# otto.net
KiCad netlist of a schematic drawn in EAGLE
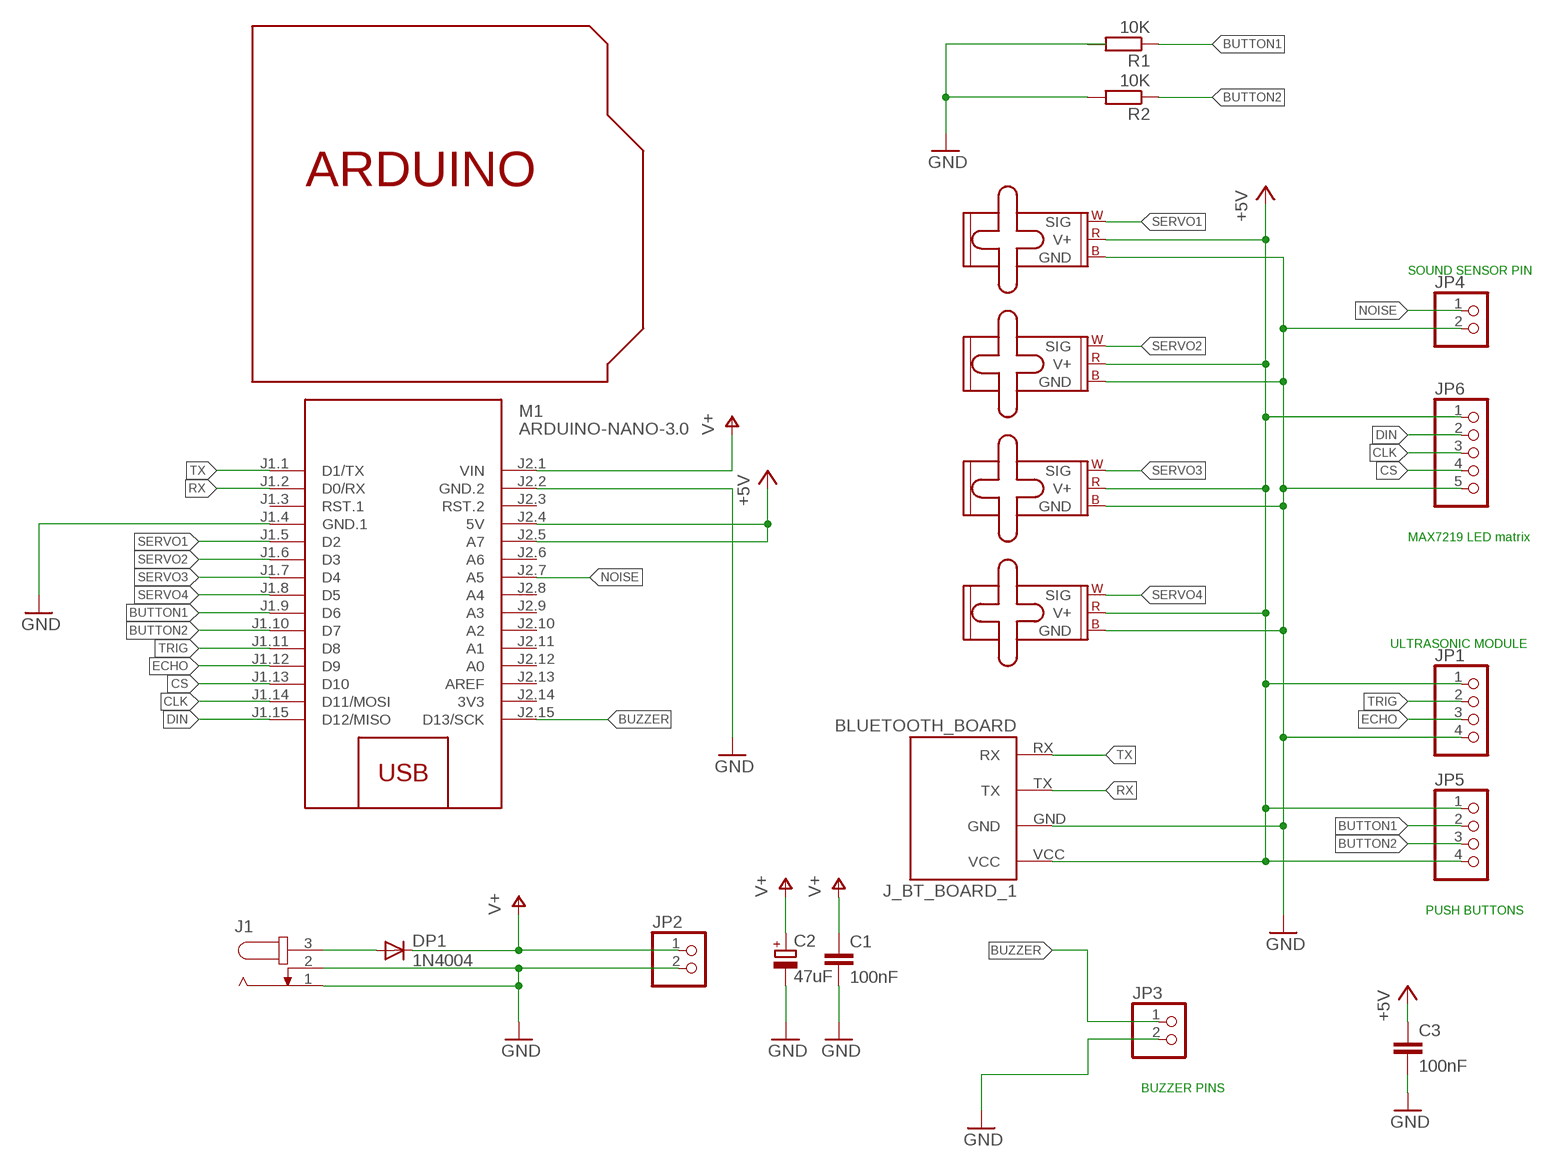
[diagram p0: schematic, sheet 1]

(export (version "E")
  (design (tool "Eeschema 10.0.6"))
  (components
    (comp (ref "C1")
      (value "100nF")
      (footprint "eagle-import:C025-025X050")
      (libsource (lib "eagle-import") (part "C-EU025-025X050"))
    )
    (comp (ref "C2")
      (value "47uF")
      (footprint "eagle-import:140CLH-0810")
      (libsource (lib "eagle-import") (part "CPOL-EU140CLH-0810"))
    )
    (comp (ref "C3")
      (value "100nF")
      (footprint "eagle-import:C025-025X050")
      (libsource (lib "eagle-import") (part "C-EU025-025X050"))
    )
    (comp (ref "DP1")
      (value "1N4004")
      (footprint "eagle-import:DO41-10")
      (libsource (lib "eagle-import") (part "1N4004"))
    )
    (comp (ref "J1")
      (value "JACK-PLUG0")
      (footprint "eagle-import:SPC4077")
      (libsource (lib "eagle-import") (part "JACK-PLUG0"))
    )
    (comp (ref "JP1")
      (value "PINHD-1X4")
      (footprint "eagle-import:1X04")
      (libsource (lib "eagle-import") (part "PINHD-1X4"))
    )
    (comp (ref "JP2")
      (value "PINHD-1X2")
      (footprint "eagle-import:1X02")
      (libsource (lib "eagle-import") (part "PINHD-1X2"))
    )
    (comp (ref "JP3")
      (value "PINHD-1X2")
      (footprint "eagle-import:1X02")
      (libsource (lib "eagle-import") (part "PINHD-1X2"))
    )
    (comp (ref "JP4")
      (value "PINHD-1X2")
      (footprint "eagle-import:1X02")
      (libsource (lib "eagle-import") (part "PINHD-1X2"))
    )
    (comp (ref "JP5")
      (value "PINHD-1X4")
      (footprint "eagle-import:1X04")
      (libsource (lib "eagle-import") (part "PINHD-1X4"))
    )
    (comp (ref "JP6")
      (value "PINHD-1X5")
      (footprint "eagle-import:1X05")
      (libsource (lib "eagle-import") (part "PINHD-1X5"))
    )
    (comp (ref "J_BT_BOARD_1")
      (value "BLUETOOTH_BOARD")
      (footprint "eagle-import:BT_BOARD_FOOTPRINT")
      (libsource (lib "eagle-import") (part "BLUETOOTH_BOARD"))
    )
    (comp (ref "M1")
      (value "ARDUINO-NANO-3.0")
      (footprint "eagle-import:ARDUINO-NANO-3.0")
      (libsource (lib "eagle-import") (part "ARDUINO-NANO-3.0"))
    )
    (comp (ref "M2")
      (value "SMALL_SERVO")
      (footprint "eagle-import:1X03")
      (libsource (lib "eagle-import") (part "SMALL_SERVO"))
    )
    (comp (ref "M3")
      (value "SMALL_SERVO")
      (footprint "eagle-import:1X03")
      (libsource (lib "eagle-import") (part "SMALL_SERVO"))
    )
    (comp (ref "M4")
      (value "SMALL_SERVO")
      (footprint "eagle-import:1X03")
      (libsource (lib "eagle-import") (part "SMALL_SERVO"))
    )
    (comp (ref "M5")
      (value "SMALL_SERVO")
      (footprint "eagle-import:1X03")
      (libsource (lib "eagle-import") (part "SMALL_SERVO"))
    )
    (comp (ref "R1")
      (value "10K")
      (footprint "eagle-import:0207_7")
      (libsource (lib "eagle-import") (part "R-EU_0207/7"))
    )
    (comp (ref "R2")
      (value "10K")
      (footprint "eagle-import:0207_7")
      (libsource (lib "eagle-import") (part "R-EU_0207/7"))
    )
    (comp (ref "U$1")
      (value "SHIELDSMALL")
      (footprint "eagle-import:ARDUINOSHIELDSMALL")
      (libsource (lib "eagle-import") (part "SHIELDSMALL"))
    )
  )
  (nets
    (net (code "1") (name "+5V") (class "Default")
      (node (ref "C3") (pin "1") (pinfunction "1_1") (pintype "passive"))
      (node (ref "JP1") (pin "1") (pinfunction "1_1") (pintype "passive"))
      (node (ref "JP5") (pin "1") (pinfunction "1_1") (pintype "passive"))
      (node (ref "JP5") (pin "4") (pinfunction "4_4") (pintype "passive"))
      (node (ref "JP6") (pin "1") (pinfunction "1_1") (pintype "passive"))
      (node (ref "J_BT_BOARD_1") (pin "VCC") (pinfunction "VCC_VCC") (pintype "bidirectional"))
      (node (ref "M1") (pin "J2.4") (pinfunction "5V_J2.4") (pintype "power_in"))
      (node (ref "M1") (pin "J2.5") (pinfunction "A7_J2.5") (pintype "bidirectional"))
      (node (ref "M2") (pin "2") (pinfunction "V+_2") (pintype "bidirectional"))
      (node (ref "M3") (pin "2") (pinfunction "V+_2") (pintype "bidirectional"))
      (node (ref "M4") (pin "2") (pinfunction "V+_2") (pintype "bidirectional"))
      (node (ref "M5") (pin "2") (pinfunction "V+_2") (pintype "bidirectional"))
    )
    (net (code "2") (name "/3V3") (class "Default")
      (node (ref "M1") (pin "J2.14") (pinfunction "3V3_J2.14") (pintype "power_in"))
    )
    (net (code "3") (name "BUTTON1") (class "Default")
      (node (ref "JP5") (pin "2") (pinfunction "2_2") (pintype "passive"))
      (node (ref "M1") (pin "J1.9") (pinfunction "D6_J1.9") (pintype "bidirectional"))
      (node (ref "R1") (pin "1") (pinfunction "1_1") (pintype "passive"))
    )
    (net (code "4") (name "BUTTON2") (class "Default")
      (node (ref "JP5") (pin "3") (pinfunction "3_3") (pintype "passive"))
      (node (ref "M1") (pin "J1.10") (pinfunction "D7_J1.10") (pintype "bidirectional"))
      (node (ref "R2") (pin "1") (pinfunction "1_1") (pintype "passive"))
    )
    (net (code "5") (name "BUZZER") (class "Default")
      (node (ref "JP3") (pin "1") (pinfunction "1_1") (pintype "passive"))
      (node (ref "M1") (pin "J2.15") (pinfunction "D13/SCK_J2.15") (pintype "bidirectional"))
    )
    (net (code "6") (name "CLK") (class "Default")
      (node (ref "JP6") (pin "3") (pinfunction "3_3") (pintype "passive"))
      (node (ref "M1") (pin "J1.14") (pinfunction "D11/MOSI_J1.14") (pintype "bidirectional"))
    )
    (net (code "7") (name "CS") (class "Default")
      (node (ref "JP6") (pin "4") (pinfunction "4_4") (pintype "passive"))
      (node (ref "M1") (pin "J1.13") (pinfunction "D10_J1.13") (pintype "bidirectional"))
    )
    (net (code "8") (name "DIN") (class "Default")
      (node (ref "JP6") (pin "2") (pinfunction "2_2") (pintype "passive"))
      (node (ref "M1") (pin "J1.15") (pinfunction "D12/MISO_J1.15") (pintype "bidirectional"))
    )
    (net (code "9") (name "ECHO") (class "Default")
      (node (ref "JP1") (pin "3") (pinfunction "3_3") (pintype "passive"))
      (node (ref "M1") (pin "J1.12") (pinfunction "D9_J1.12") (pintype "bidirectional"))
    )
    (net (code "10") (name "GND") (class "Default")
      (node (ref "C1") (pin "2") (pinfunction "2_2") (pintype "passive"))
      (node (ref "C2") (pin "-") (pinfunction "-_-") (pintype "passive"))
      (node (ref "C3") (pin "2") (pinfunction "2_2") (pintype "passive"))
      (node (ref "J1") (pin "1") (pinfunction "1_1") (pintype "passive"))
      (node (ref "J1") (pin "2") (pinfunction "2_2") (pintype "passive"))
      (node (ref "JP1") (pin "4") (pinfunction "4_4") (pintype "passive"))
      (node (ref "JP2") (pin "2") (pinfunction "2_2") (pintype "passive"))
      (node (ref "JP3") (pin "2") (pinfunction "2_2") (pintype "passive"))
      (node (ref "JP4") (pin "2") (pinfunction "2_2") (pintype "passive"))
      (node (ref "JP6") (pin "5") (pinfunction "5_5") (pintype "passive"))
      (node (ref "J_BT_BOARD_1") (pin "GND") (pinfunction "GND_GND") (pintype "bidirectional"))
      (node (ref "M1") (pin "J1.4") (pinfunction "GND.1_J1.4") (pintype "power_in"))
      (node (ref "M1") (pin "J2.2") (pinfunction "GND.2_J2.2") (pintype "power_in"))
      (node (ref "M2") (pin "3") (pinfunction "GND_3") (pintype "bidirectional"))
      (node (ref "M3") (pin "3") (pinfunction "GND_3") (pintype "bidirectional"))
      (node (ref "M4") (pin "3") (pinfunction "GND_3") (pintype "bidirectional"))
      (node (ref "M5") (pin "3") (pinfunction "GND_3") (pintype "bidirectional"))
      (node (ref "R2") (pin "2") (pinfunction "2_2") (pintype "passive"))
    )
    (net (code "11") (name "NOISE") (class "Default")
      (node (ref "JP4") (pin "1") (pinfunction "1_1") (pintype "passive"))
      (node (ref "M1") (pin "J2.7") (pinfunction "A5_J2.7") (pintype "bidirectional"))
    )
    (net (code "12") (name "Net-(DP1-PadA)") (class "Default")
      (node (ref "DP1") (pin "A") (pinfunction "A_A") (pintype "passive"))
      (node (ref "J1") (pin "3") (pinfunction "3_3") (pintype "passive"))
    )
    (net (code "13") (name "RX") (class "Default")
      (node (ref "J_BT_BOARD_1") (pin "TX") (pinfunction "TX_TX") (pintype "bidirectional"))
      (node (ref "M1") (pin "J1.2") (pinfunction "D0/RX_J1.2") (pintype "bidirectional"))
    )
    (net (code "14") (name "SERVO1") (class "Default")
      (node (ref "M1") (pin "J1.5") (pinfunction "D2_J1.5") (pintype "bidirectional"))
      (node (ref "M2") (pin "1") (pinfunction "SIG_1") (pintype "bidirectional"))
    )
    (net (code "15") (name "SERVO2") (class "Default")
      (node (ref "M1") (pin "J1.6") (pinfunction "D3_J1.6") (pintype "bidirectional"))
      (node (ref "M3") (pin "1") (pinfunction "SIG_1") (pintype "bidirectional"))
    )
    (net (code "16") (name "SERVO3") (class "Default")
      (node (ref "M1") (pin "J1.7") (pinfunction "D4_J1.7") (pintype "bidirectional"))
      (node (ref "M4") (pin "1") (pinfunction "SIG_1") (pintype "bidirectional"))
    )
    (net (code "17") (name "SERVO4") (class "Default")
      (node (ref "M1") (pin "J1.8") (pinfunction "D5_J1.8") (pintype "bidirectional"))
      (node (ref "M5") (pin "1") (pinfunction "SIG_1") (pintype "bidirectional"))
    )
    (net (code "18") (name "TRIG") (class "Default")
      (node (ref "JP1") (pin "2") (pinfunction "2_2") (pintype "passive"))
      (node (ref "M1") (pin "J1.11") (pinfunction "D8_J1.11") (pintype "bidirectional"))
    )
    (net (code "19") (name "TX") (class "Default")
      (node (ref "J_BT_BOARD_1") (pin "RX") (pinfunction "RX_RX") (pintype "bidirectional"))
      (node (ref "M1") (pin "J1.1") (pinfunction "D1/TX_J1.1") (pintype "bidirectional"))
    )
    (net (code "20") (name "V+") (class "Default")
      (node (ref "C1") (pin "1") (pinfunction "1_1") (pintype "passive"))
      (node (ref "C2") (pin "+") (pinfunction "+_+") (pintype "passive"))
      (node (ref "DP1") (pin "C") (pinfunction "C_C") (pintype "passive"))
      (node (ref "JP2") (pin "1") (pinfunction "1_1") (pintype "passive"))
      (node (ref "M1") (pin "J2.1") (pinfunction "VIN_J2.1") (pintype "power_in"))
    )
    (net (code "21") (name "unconnected-(M1-A0-PadJ2.12)") (class "Default")
      (node (ref "M1") (pin "J2.12") (pinfunction "A0_J2.12") (pintype "bidirectional"))
    )
    (net (code "22") (name "unconnected-(M1-A1-PadJ2.11)") (class "Default")
      (node (ref "M1") (pin "J2.11") (pinfunction "A1_J2.11") (pintype "bidirectional"))
    )
    (net (code "23") (name "unconnected-(M1-A2-PadJ2.10)") (class "Default")
      (node (ref "M1") (pin "J2.10") (pinfunction "A2_J2.10") (pintype "bidirectional"))
    )
    (net (code "24") (name "unconnected-(M1-A3-PadJ2.9)") (class "Default")
      (node (ref "M1") (pin "J2.9") (pinfunction "A3_J2.9") (pintype "bidirectional"))
    )
    (net (code "25") (name "unconnected-(M1-A4-PadJ2.8)") (class "Default")
      (node (ref "M1") (pin "J2.8") (pinfunction "A4_J2.8") (pintype "bidirectional"))
    )
    (net (code "26") (name "unconnected-(M1-A6-PadJ2.6)") (class "Default")
      (node (ref "M1") (pin "J2.6") (pinfunction "A6_J2.6") (pintype "bidirectional"))
    )
    (net (code "27") (name "unconnected-(M1-AREF-PadJ2.13)") (class "Default")
      (node (ref "M1") (pin "J2.13") (pinfunction "AREF_J2.13") (pintype "bidirectional"))
    )
    (net (code "28") (name "unconnected-(M1-RST.1-PadJ1.3)") (class "Default")
      (node (ref "M1") (pin "J1.3") (pinfunction "RST.1_J1.3") (pintype "bidirectional"))
    )
    (net (code "29") (name "unconnected-(M1-RST.2-PadJ2.3)") (class "Default")
      (node (ref "M1") (pin "J2.3") (pinfunction "RST.2_J2.3") (pintype "bidirectional"))
    )
    (net (code "30") (name "unconnected-(R1-Pad2)") (class "Default")
      (node (ref "R1") (pin "2") (pinfunction "2_2") (pintype "passive"))
    )
  )
)
